# lampica.net
KiCad netlist of a schematic drawn in EAGLE
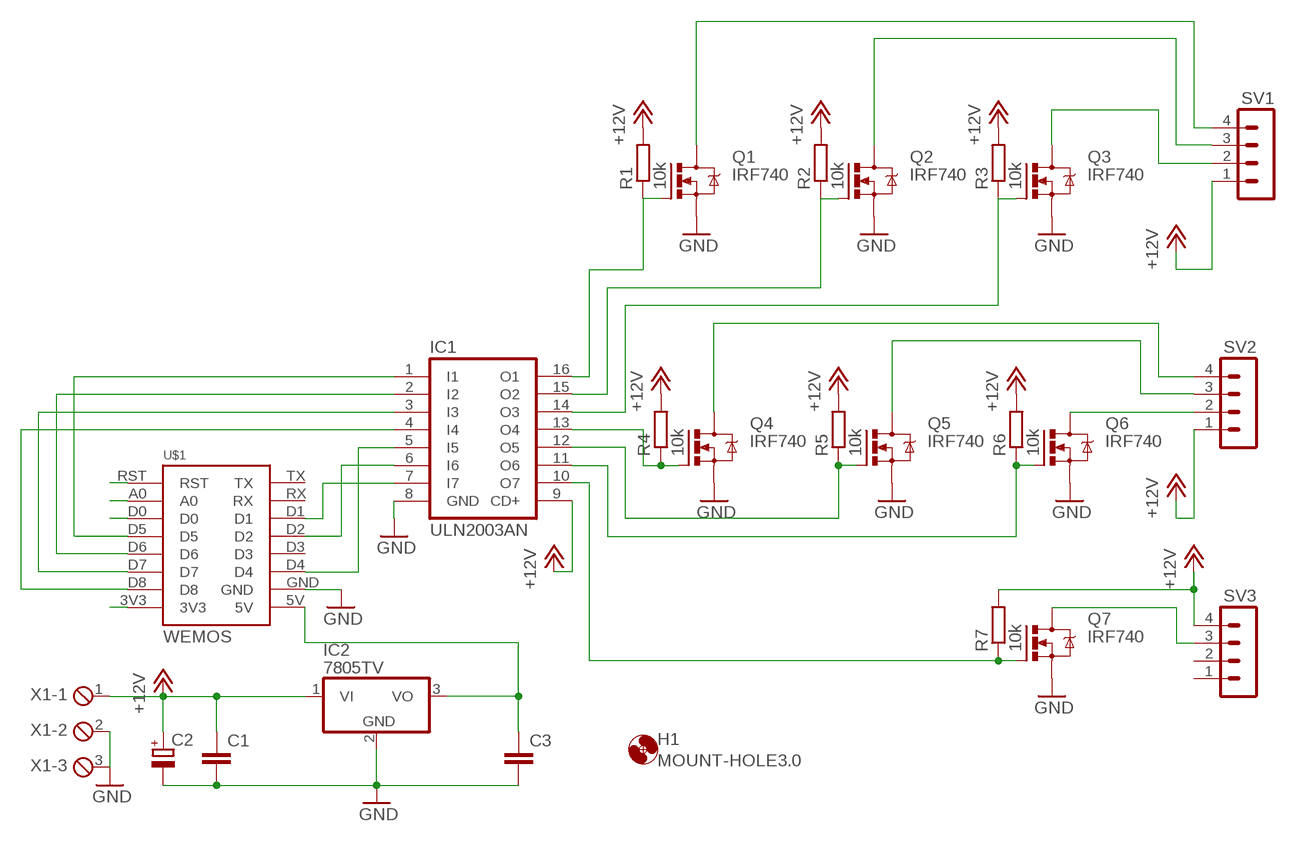
[diagram p0: schematic, sheet 1]

(export (version "E")
  (design (tool "Eeschema 10.0.6"))
  (components
    (comp (ref "C1")
      (value "C-EU050-025X075")
      (footprint "eagle-import:C050-025X075")
      (libsource (lib "eagle-import") (part "C-EU050-025X075"))
    )
    (comp (ref "C2")
      (value "CPOL-EUE5-8.5")
      (footprint "eagle-import:E5-8,5")
      (libsource (lib "eagle-import") (part "CPOL-EUE5-8.5"))
    )
    (comp (ref "C3")
      (value "C-EU050-025X075")
      (footprint "eagle-import:C050-025X075")
      (libsource (lib "eagle-import") (part "C-EU050-025X075"))
    )
    (comp (ref "H1")
      (value "MOUNT-HOLE3.0")
      (footprint "eagle-import:3,0")
      (libsource (lib "eagle-import") (part "MOUNT-HOLE3.0"))
    )
    (comp (ref "IC1")
      (value "ULN2003AN")
      (footprint "eagle-import:DIL16")
      (libsource (lib "eagle-import") (part "ULN2003AN"))
    )
    (comp (ref "IC2")
      (value "7805TV")
      (footprint "eagle-import:TO220V")
      (libsource (lib "eagle-import") (part "78TV05"))
    )
    (comp (ref "Q1")
      (value "IRF740")
      (footprint "eagle-import:TO220BV")
      (libsource (lib "eagle-import") (part "IRF740"))
    )
    (comp (ref "Q2")
      (value "IRF740")
      (footprint "eagle-import:TO220BV")
      (libsource (lib "eagle-import") (part "IRF740"))
    )
    (comp (ref "Q3")
      (value "IRF740")
      (footprint "eagle-import:TO220BV")
      (libsource (lib "eagle-import") (part "IRF740"))
    )
    (comp (ref "Q4")
      (value "IRF740")
      (footprint "eagle-import:TO220BV")
      (libsource (lib "eagle-import") (part "IRF740"))
    )
    (comp (ref "Q5")
      (value "IRF740")
      (footprint "eagle-import:TO220BV")
      (libsource (lib "eagle-import") (part "IRF740"))
    )
    (comp (ref "Q6")
      (value "IRF740")
      (footprint "eagle-import:TO220BV")
      (libsource (lib "eagle-import") (part "IRF740"))
    )
    (comp (ref "Q7")
      (value "IRF740")
      (footprint "eagle-import:TO220BV")
      (libsource (lib "eagle-import") (part "IRF740"))
    )
    (comp (ref "R1")
      (value "10k")
      (footprint "eagle-import:0207_7")
      (libsource (lib "eagle-import") (part "R-EU_0207/7"))
    )
    (comp (ref "R2")
      (value "10k")
      (footprint "eagle-import:0207_7")
      (libsource (lib "eagle-import") (part "R-EU_0207/7"))
    )
    (comp (ref "R3")
      (value "10k")
      (footprint "eagle-import:0207_7")
      (libsource (lib "eagle-import") (part "R-EU_0207/7"))
    )
    (comp (ref "R4")
      (value "10k")
      (footprint "eagle-import:0207_10")
      (libsource (lib "eagle-import") (part "R-EU_0207/10"))
    )
    (comp (ref "R5")
      (value "10k")
      (footprint "eagle-import:0207_7")
      (libsource (lib "eagle-import") (part "R-EU_0207/7"))
    )
    (comp (ref "R6")
      (value "10k")
      (footprint "eagle-import:0207_7")
      (libsource (lib "eagle-import") (part "R-EU_0207/7"))
    )
    (comp (ref "R7")
      (value "10k")
      (footprint "eagle-import:0207_7")
      (libsource (lib "eagle-import") (part "R-EU_0207/7"))
    )
    (comp (ref "SV1")
      (value "MA04-1")
      (footprint "eagle-import:MA04-1")
      (libsource (lib "eagle-import") (part "MA04-1"))
    )
    (comp (ref "SV2")
      (value "MA04-1")
      (footprint "eagle-import:MA04-1")
      (libsource (lib "eagle-import") (part "MA04-1"))
    )
    (comp (ref "SV3")
      (value "MA04-1")
      (footprint "eagle-import:MA04-1")
      (libsource (lib "eagle-import") (part "MA04-1"))
    )
    (comp (ref "U$1")
      (value "WEMOS")
      (footprint "eagle-import:WEMOS")
      (libsource (lib "eagle-import") (part "WEMOS"))
    )
    (comp (ref "X1")
      (value "MPT3")
      (footprint "eagle-import:3POL254")
      (libsource (lib "eagle-import") (part "MPT3"))
    )
  )
  (nets
    (net (code "1") (name "+12V") (class "Default")
      (node (ref "C1") (pin "1") (pinfunction "1_1") (pintype "passive"))
      (node (ref "C2") (pin "+") (pinfunction "+_+") (pintype "passive"))
      (node (ref "IC1") (pin "9") (pinfunction "CD+_9") (pintype "passive"))
      (node (ref "IC2") (pin "1") (pinfunction "VI_1") (pintype "input"))
      (node (ref "R1") (pin "2") (pinfunction "2_2") (pintype "passive"))
      (node (ref "R2") (pin "2") (pinfunction "2_2") (pintype "passive"))
      (node (ref "R3") (pin "2") (pinfunction "2_2") (pintype "passive"))
      (node (ref "R4") (pin "2") (pinfunction "2_2") (pintype "passive"))
      (node (ref "R5") (pin "2") (pinfunction "2_2") (pintype "passive"))
      (node (ref "R6") (pin "2") (pinfunction "2_2") (pintype "passive"))
      (node (ref "R7") (pin "2") (pinfunction "2_2") (pintype "passive"))
      (node (ref "SV1") (pin "1") (pinfunction "1_1") (pintype "passive"))
      (node (ref "SV2") (pin "1") (pinfunction "1_1") (pintype "passive"))
      (node (ref "SV3") (pin "4") (pinfunction "4_4") (pintype "passive"))
      (node (ref "X1") (pin "1") (pinfunction "1_1") (pintype "passive"))
    )
    (net (code "2") (name "GND") (class "Default")
      (node (ref "C1") (pin "2") (pinfunction "2_2") (pintype "passive"))
      (node (ref "C2") (pin "-") (pinfunction "-_-") (pintype "passive"))
      (node (ref "C3") (pin "2") (pinfunction "2_2") (pintype "passive"))
      (node (ref "IC1") (pin "8") (pinfunction "GND_8") (pintype "power_in"))
      (node (ref "IC2") (pin "2") (pinfunction "GND_2") (pintype "passive"))
      (node (ref "Q1") (pin "S") (pinfunction "S_S") (pintype "passive"))
      (node (ref "Q2") (pin "S") (pinfunction "S_S") (pintype "passive"))
      (node (ref "Q3") (pin "S") (pinfunction "S_S") (pintype "passive"))
      (node (ref "Q4") (pin "S") (pinfunction "S_S") (pintype "passive"))
      (node (ref "Q5") (pin "S") (pinfunction "S_S") (pintype "passive"))
      (node (ref "Q6") (pin "S") (pinfunction "S_S") (pintype "passive"))
      (node (ref "Q7") (pin "S") (pinfunction "S_S") (pintype "passive"))
      (node (ref "U$1") (pin "GND") (pinfunction "GND_GND") (pintype "bidirectional"))
      (node (ref "X1") (pin "2") (pinfunction "1_2") (pintype "passive"))
      (node (ref "X1") (pin "3") (pinfunction "1_3") (pintype "passive"))
    )
    (net (code "3") (name "Net-(IC1-I1)") (class "Default")
      (node (ref "IC1") (pin "1") (pinfunction "I1_1") (pintype "input"))
      (node (ref "U$1") (pin "D5") (pinfunction "D5_D5") (pintype "bidirectional"))
    )
    (net (code "4") (name "Net-(IC1-I2)") (class "Default")
      (node (ref "IC1") (pin "2") (pinfunction "I2_2") (pintype "input"))
      (node (ref "U$1") (pin "D6") (pinfunction "D6_D6") (pintype "bidirectional"))
    )
    (net (code "5") (name "Net-(IC1-I3)") (class "Default")
      (node (ref "IC1") (pin "3") (pinfunction "I3_3") (pintype "input"))
      (node (ref "U$1") (pin "D7") (pinfunction "D7_D7") (pintype "bidirectional"))
    )
    (net (code "6") (name "Net-(IC1-I4)") (class "Default")
      (node (ref "IC1") (pin "4") (pinfunction "I4_4") (pintype "input"))
      (node (ref "U$1") (pin "D8") (pinfunction "D8_D8") (pintype "bidirectional"))
    )
    (net (code "7") (name "Net-(IC1-I5)") (class "Default")
      (node (ref "IC1") (pin "5") (pinfunction "I5_5") (pintype "input"))
      (node (ref "U$1") (pin "D4") (pinfunction "D4_D4") (pintype "bidirectional"))
    )
    (net (code "8") (name "Net-(IC1-I6)") (class "Default")
      (node (ref "IC1") (pin "6") (pinfunction "I6_6") (pintype "input"))
      (node (ref "U$1") (pin "D2") (pinfunction "D2_D2") (pintype "bidirectional"))
    )
    (net (code "9") (name "Net-(IC1-I7)") (class "Default")
      (node (ref "IC1") (pin "7") (pinfunction "I7_7") (pintype "input"))
      (node (ref "U$1") (pin "D1") (pinfunction "D1_D1") (pintype "bidirectional"))
    )
    (net (code "10") (name "Net-(IC1-O1)") (class "Default")
      (node (ref "IC1") (pin "16") (pinfunction "O1_16") (pintype "open_collector"))
      (node (ref "Q1") (pin "G") (pinfunction "G_G") (pintype "passive"))
      (node (ref "R1") (pin "1") (pinfunction "1_1") (pintype "passive"))
    )
    (net (code "11") (name "Net-(IC1-O2)") (class "Default")
      (node (ref "IC1") (pin "15") (pinfunction "O2_15") (pintype "open_collector"))
      (node (ref "Q2") (pin "G") (pinfunction "G_G") (pintype "passive"))
      (node (ref "R2") (pin "1") (pinfunction "1_1") (pintype "passive"))
    )
    (net (code "12") (name "Net-(IC1-O3)") (class "Default")
      (node (ref "IC1") (pin "14") (pinfunction "O3_14") (pintype "open_collector"))
      (node (ref "Q3") (pin "G") (pinfunction "G_G") (pintype "passive"))
      (node (ref "R3") (pin "1") (pinfunction "1_1") (pintype "passive"))
    )
    (net (code "13") (name "Net-(IC1-O4)") (class "Default")
      (node (ref "IC1") (pin "13") (pinfunction "O4_13") (pintype "open_collector"))
      (node (ref "Q4") (pin "G") (pinfunction "G_G") (pintype "passive"))
      (node (ref "R4") (pin "1") (pinfunction "1_1") (pintype "passive"))
    )
    (net (code "14") (name "Net-(IC1-O5)") (class "Default")
      (node (ref "IC1") (pin "12") (pinfunction "O5_12") (pintype "open_collector"))
      (node (ref "Q5") (pin "G") (pinfunction "G_G") (pintype "passive"))
      (node (ref "R5") (pin "1") (pinfunction "1_1") (pintype "passive"))
    )
    (net (code "15") (name "Net-(IC1-O6)") (class "Default")
      (node (ref "IC1") (pin "11") (pinfunction "O6_11") (pintype "open_collector"))
      (node (ref "Q6") (pin "G") (pinfunction "G_G") (pintype "passive"))
      (node (ref "R6") (pin "1") (pinfunction "1_1") (pintype "passive"))
    )
    (net (code "16") (name "Net-(IC1-O7)") (class "Default")
      (node (ref "IC1") (pin "10") (pinfunction "O7_10") (pintype "open_collector"))
      (node (ref "Q7") (pin "G") (pinfunction "G_G") (pintype "passive"))
      (node (ref "R7") (pin "1") (pinfunction "1_1") (pintype "passive"))
    )
    (net (code "17") (name "Net-(IC2-VO)") (class "Default")
      (node (ref "C3") (pin "1") (pinfunction "1_1") (pintype "passive"))
      (node (ref "IC2") (pin "3") (pinfunction "VO_3") (pintype "passive"))
      (node (ref "U$1") (pin "5V") (pinfunction "5V_5V") (pintype "bidirectional"))
    )
    (net (code "18") (name "Net-(Q1-PadD)") (class "Default")
      (node (ref "Q1") (pin "D") (pinfunction "D_D") (pintype "passive"))
      (node (ref "SV1") (pin "4") (pinfunction "4_4") (pintype "passive"))
    )
    (net (code "19") (name "Net-(Q2-PadD)") (class "Default")
      (node (ref "Q2") (pin "D") (pinfunction "D_D") (pintype "passive"))
      (node (ref "SV1") (pin "3") (pinfunction "3_3") (pintype "passive"))
    )
    (net (code "20") (name "Net-(Q3-PadD)") (class "Default")
      (node (ref "Q3") (pin "D") (pinfunction "D_D") (pintype "passive"))
      (node (ref "SV1") (pin "2") (pinfunction "2_2") (pintype "passive"))
    )
    (net (code "21") (name "Net-(Q4-PadD)") (class "Default")
      (node (ref "Q4") (pin "D") (pinfunction "D_D") (pintype "passive"))
      (node (ref "SV2") (pin "4") (pinfunction "4_4") (pintype "passive"))
    )
    (net (code "22") (name "Net-(Q5-PadD)") (class "Default")
      (node (ref "Q5") (pin "D") (pinfunction "D_D") (pintype "passive"))
      (node (ref "SV2") (pin "3") (pinfunction "3_3") (pintype "passive"))
    )
    (net (code "23") (name "Net-(Q6-PadD)") (class "Default")
      (node (ref "Q6") (pin "D") (pinfunction "D_D") (pintype "passive"))
      (node (ref "SV2") (pin "2") (pinfunction "2_2") (pintype "passive"))
    )
    (net (code "24") (name "Net-(Q7-PadD)") (class "Default")
      (node (ref "Q7") (pin "D") (pinfunction "D_D") (pintype "passive"))
      (node (ref "SV3") (pin "3") (pinfunction "3_3") (pintype "passive"))
    )
    (net (code "25") (name "unconnected-(SV3-Pad1)") (class "Default")
      (node (ref "SV3") (pin "1") (pinfunction "1_1") (pintype "passive"))
    )
    (net (code "26") (name "unconnected-(SV3-Pad2)") (class "Default")
      (node (ref "SV3") (pin "2") (pinfunction "2_2") (pintype "passive"))
    )
    (net (code "27") (name "unconnected-(U$1-Pad3V3)") (class "Default")
      (node (ref "U$1") (pin "3V3") (pinfunction "3V3_3V3") (pintype "bidirectional"))
    )
    (net (code "28") (name "unconnected-(U$1-PadA0)") (class "Default")
      (node (ref "U$1") (pin "A0") (pinfunction "A0_A0") (pintype "bidirectional"))
    )
    (net (code "29") (name "unconnected-(U$1-PadD0)") (class "Default")
      (node (ref "U$1") (pin "D0") (pinfunction "D0_D0") (pintype "bidirectional"))
    )
    (net (code "30") (name "unconnected-(U$1-PadD3)") (class "Default")
      (node (ref "U$1") (pin "D3") (pinfunction "D3_D3") (pintype "bidirectional"))
    )
    (net (code "31") (name "unconnected-(U$1-PadRST)") (class "Default")
      (node (ref "U$1") (pin "RST") (pinfunction "RST_RST") (pintype "bidirectional"))
    )
    (net (code "32") (name "unconnected-(U$1-PadRX)") (class "Default")
      (node (ref "U$1") (pin "RX") (pinfunction "RX_RX") (pintype "bidirectional"))
    )
    (net (code "33") (name "unconnected-(U$1-PadTX)") (class "Default")
      (node (ref "U$1") (pin "TX") (pinfunction "TX_TX") (pintype "bidirectional"))
    )
  )
)
